# V_3.net
KiCad netlist of a schematic drawn in Altium Designer
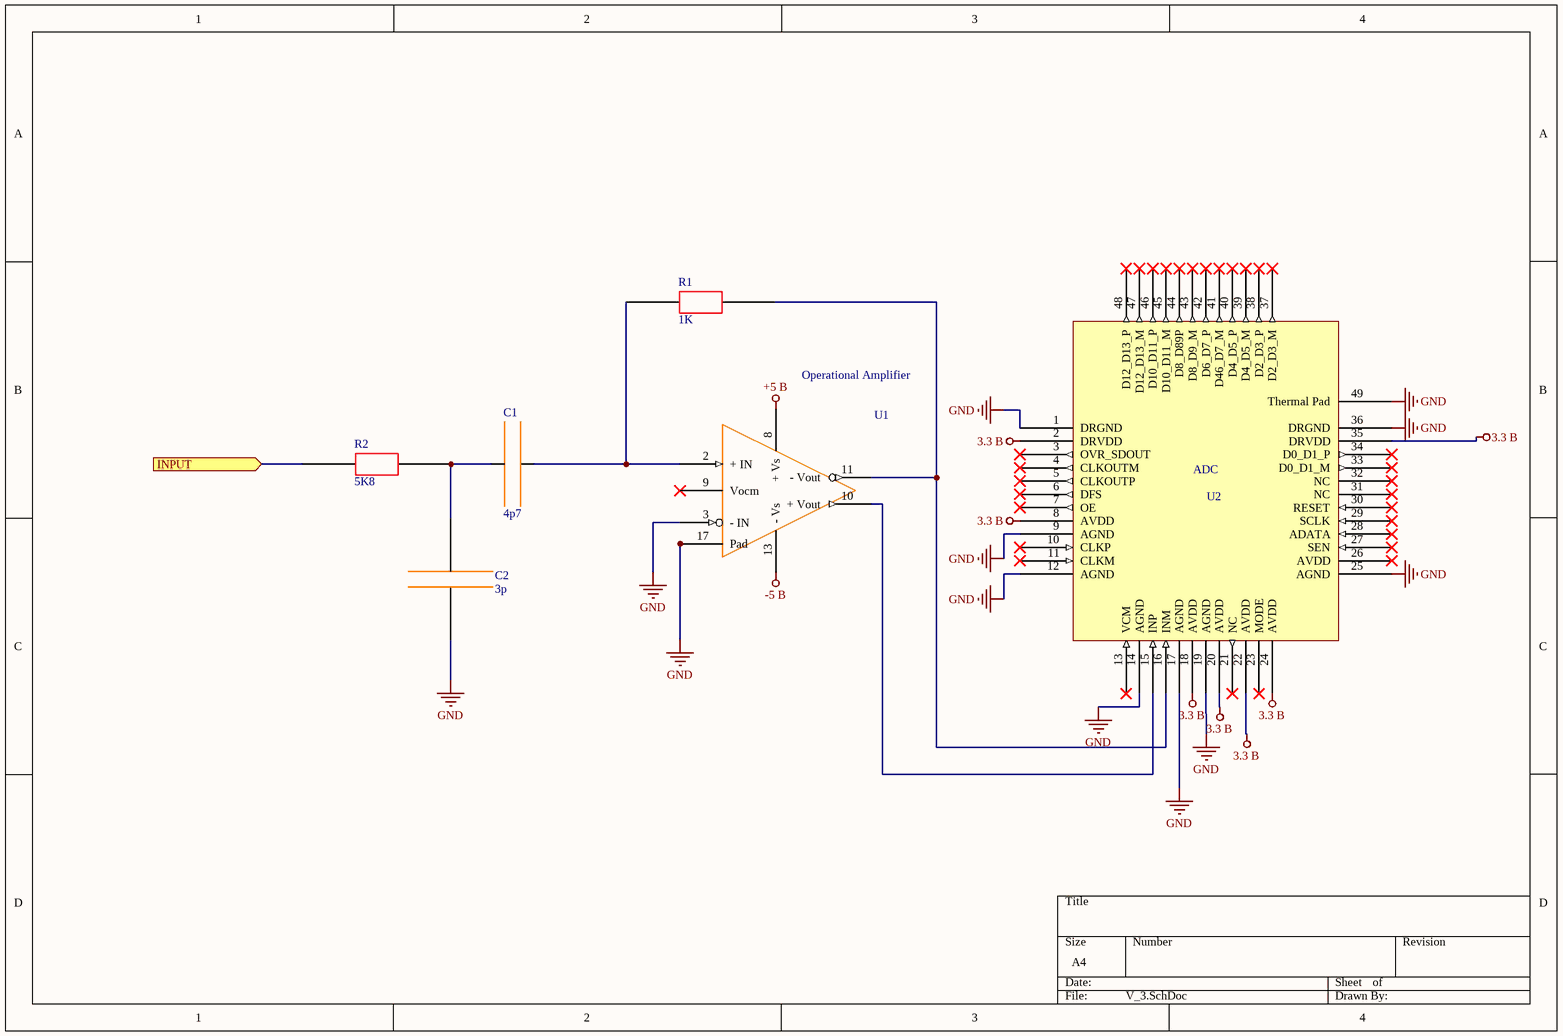
[diagram p0: V_3.SchDoc]

(export (version "E")
  (design (tool "Eeschema 10.0.6"))
  (components
    (comp (ref "C1") (value "4p7") (footprint "V_3:C_0805") (libsource (lib "") (part "Condenser_1")))
    (comp (ref "C2") (value "3p") (footprint "V_3:C_0805") (libsource (lib "V_3") (part "Condenser")))
    (comp (ref "R1") (value "1K") (footprint "V_3:R_0805") (libsource (lib "V_3") (part "Resistor")))
    (comp (ref "R2") (value "5K8") (footprint "V_3:R_0805") (libsource (lib "V_3") (part "Resistor")))
    (comp (ref "U1")
      (value "Operational Amplifier")
      (footprint "V_3:ADA4932-1")
      (libsource (lib "V_3") (part "Operational Amplifier"))
    )
    (comp (ref "U2") (value "ADC") (footprint "V_3:ADS61B49") (libsource (lib "V_3") (part "ADC")))
  )
  (nets
    (net (code "1") (name "+5 B") (class "Default")
      (node (ref "U1") (pin "8") (pinfunction "+_Vs_8") (pintype "passive"))
    )
    (net (code "2") (name "-5 B") (class "Default")
      (node (ref "U1") (pin "13") (pinfunction "-_Vs_13") (pintype "passive"))
    )
    (net (code "3") (name "/INPUT") (class "Default")
      (node (ref "R2") (pin "1") (pinfunction "1_1") (pintype "passive"))
    )
    (net (code "4") (name "3.3 B") (class "Default")
      (node (ref "U2") (pin "18") (pinfunction "AVDD_18") (pintype "power_in"))
      (node (ref "U2") (pin "2") (pinfunction "DRVDD_2") (pintype "power_in"))
      (node (ref "U2") (pin "20") (pinfunction "AVDD_20") (pintype "power_in"))
      (node (ref "U2") (pin "22") (pinfunction "AVDD_22") (pintype "power_in"))
      (node (ref "U2") (pin "24") (pinfunction "AVDD_24") (pintype "power_in"))
      (node (ref "U2") (pin "35") (pinfunction "DRVDD_35") (pintype "power_in"))
      (node (ref "U2") (pin "8") (pinfunction "AVDD_8") (pintype "power_in"))
    )
    (net (code "5") (name "GND") (class "Default")
      (node (ref "C2") (pin "3") (pinfunction "3_3") (pintype "passive"))
      (node (ref "U1") (pin "17") (pinfunction "Pad_17") (pintype "power_in"))
      (node (ref "U1") (pin "3") (pinfunction "-_IN_3") (pintype "input"))
      (node (ref "U2") (pin "1") (pinfunction "DRGND_1") (pintype "power_in"))
      (node (ref "U2") (pin "12") (pinfunction "AGND_12") (pintype "power_in"))
      (node (ref "U2") (pin "14") (pinfunction "AGND_14") (pintype "power_in"))
      (node (ref "U2") (pin "17") (pinfunction "AGND_17") (pintype "power_in"))
      (node (ref "U2") (pin "19") (pinfunction "AGND_19") (pintype "power_in"))
      (node (ref "U2") (pin "25") (pinfunction "AGND_25") (pintype "power_in"))
      (node (ref "U2") (pin "36") (pinfunction "DRGND_36") (pintype "power_in"))
      (node (ref "U2") (pin "49") (pinfunction "Thermal_Pad_49") (pintype "power_in"))
      (node (ref "U2") (pin "9") (pinfunction "AGND_9") (pintype "power_in"))
    )
    (net (code "6") (name "Net-(C1-Pad4)") (class "Default")
      (node (ref "C1") (pin "4") (pinfunction "4_4") (pintype "passive"))
      (node (ref "C2") (pin "4") (pinfunction "4_4") (pintype "passive"))
      (node (ref "R2") (pin "2") (pinfunction "2_2") (pintype "passive"))
    )
    (net (code "7") (name "Net-(U1-+_IN)") (class "Default")
      (node (ref "C1") (pin "3") (pinfunction "3_3") (pintype "passive"))
      (node (ref "R1") (pin "1") (pinfunction "1_1") (pintype "passive"))
      (node (ref "U1") (pin "2") (pinfunction "+_IN_2") (pintype "input"))
    )
    (net (code "8") (name "Net-(U1-+_Vout)") (class "Default")
      (node (ref "U1") (pin "10") (pinfunction "+_Vout_10") (pintype "output"))
      (node (ref "U2") (pin "15") (pinfunction "INP_15") (pintype "input"))
    )
    (net (code "9") (name "Net-(U1--_Vout)") (class "Default")
      (node (ref "R1") (pin "2") (pinfunction "2_2") (pintype "passive"))
      (node (ref "U1") (pin "11") (pinfunction "-_Vout_11") (pintype "output"))
      (node (ref "U2") (pin "16") (pinfunction "INM_16") (pintype "input"))
    )
    (net (code "10") (name "unconnected-(U1-Vocm-Pad9)") (class "Default")
      (node (ref "U1") (pin "9") (pinfunction "Vocm_9") (pintype "passive+no_connect"))
    )
    (net (code "11") (name "unconnected-(U2-ADATA-Pad28)") (class "Default")
      (node (ref "U2") (pin "28") (pinfunction "ADATA_28") (pintype "input+no_connect"))
    )
    (net (code "12") (name "unconnected-(U2-AVDD-Pad26)") (class "Default")
      (node (ref "U2") (pin "26") (pinfunction "AVDD_26") (pintype "power_in+no_connect"))
    )
    (net (code "13") (name "unconnected-(U2-CLKM-Pad11)") (class "Default")
      (node (ref "U2") (pin "11") (pinfunction "CLKM_11") (pintype "input+no_connect"))
    )
    (net (code "14") (name "unconnected-(U2-CLKOUTM-Pad4)") (class "Default")
      (node (ref "U2") (pin "4") (pinfunction "CLKOUTM_4") (pintype "output+no_connect"))
    )
    (net (code "15") (name "unconnected-(U2-CLKOUTP-Pad5)") (class "Default")
      (node (ref "U2") (pin "5") (pinfunction "CLKOUTP_5") (pintype "output+no_connect"))
    )
    (net (code "16") (name "unconnected-(U2-CLKP-Pad10)") (class "Default")
      (node (ref "U2") (pin "10") (pinfunction "CLKP_10") (pintype "input+no_connect"))
    )
    (net (code "17") (name "unconnected-(U2-D0_D1_M-Pad33)") (class "Default")
      (node (ref "U2") (pin "33") (pinfunction "D0_D1_M_33") (pintype "output+no_connect"))
    )
    (net (code "18") (name "unconnected-(U2-D0_D1_P-Pad34)") (class "Default")
      (node (ref "U2") (pin "34") (pinfunction "D0_D1_P_34") (pintype "output+no_connect"))
    )
    (net (code "19") (name "unconnected-(U2-D2_D3_M-Pad37)") (class "Default")
      (node (ref "U2") (pin "37") (pinfunction "D2_D3_M_37") (pintype "output+no_connect"))
    )
    (net (code "20") (name "unconnected-(U2-D2_D3_P-Pad38)") (class "Default")
      (node (ref "U2") (pin "38") (pinfunction "D2_D3_P_38") (pintype "output+no_connect"))
    )
    (net (code "21") (name "unconnected-(U2-D4_D5_M-Pad39)") (class "Default")
      (node (ref "U2") (pin "39") (pinfunction "D4_D5_M_39") (pintype "output+no_connect"))
    )
    (net (code "22") (name "unconnected-(U2-D4_D5_P-Pad40)") (class "Default")
      (node (ref "U2") (pin "40") (pinfunction "D4_D5_P_40") (pintype "output+no_connect"))
    )
    (net (code "23") (name "unconnected-(U2-D6_D7_P-Pad42)") (class "Default")
      (node (ref "U2") (pin "42") (pinfunction "D6_D7_P_42") (pintype "output+no_connect"))
    )
    (net (code "24") (name "unconnected-(U2-D8_D9_M-Pad43)") (class "Default")
      (node (ref "U2") (pin "43") (pinfunction "D8_D9_M_43") (pintype "output+no_connect"))
    )
    (net (code "25") (name "unconnected-(U2-D8_D89P-Pad44)") (class "Default")
      (node (ref "U2") (pin "44") (pinfunction "D8_D89P_44") (pintype "output+no_connect"))
    )
    (net (code "26") (name "unconnected-(U2-D10_D11_M-Pad45)") (class "Default")
      (node (ref "U2") (pin "45") (pinfunction "D10_D11_M_45") (pintype "output+no_connect"))
    )
    (net (code "27") (name "unconnected-(U2-D10_D11_P-Pad46)") (class "Default")
      (node (ref "U2") (pin "46") (pinfunction "D10_D11_P_46") (pintype "output+no_connect"))
    )
    (net (code "28") (name "unconnected-(U2-D12_D13_M-Pad47)") (class "Default")
      (node (ref "U2") (pin "47") (pinfunction "D12_D13_M_47") (pintype "output+no_connect"))
    )
    (net (code "29") (name "unconnected-(U2-D12_D13_P-Pad48)") (class "Default")
      (node (ref "U2") (pin "48") (pinfunction "D12_D13_P_48") (pintype "output+no_connect"))
    )
    (net (code "30") (name "unconnected-(U2-D46_D7_M-Pad41)") (class "Default")
      (node (ref "U2") (pin "41") (pinfunction "D46_D7_M_41") (pintype "output+no_connect"))
    )
    (net (code "31") (name "unconnected-(U2-DFS-Pad6)") (class "Default")
      (node (ref "U2") (pin "6") (pinfunction "DFS_6") (pintype "output+no_connect"))
    )
    (net (code "32") (name "unconnected-(U2-MODE-Pad23)") (class "Default")
      (node (ref "U2") (pin "23") (pinfunction "MODE_23") (pintype "power_in+no_connect"))
    )
    (net (code "33") (name "unconnected-(U2-NC-Pad21)") (class "Default")
      (node (ref "U2") (pin "21") (pinfunction "NC_21") (pintype "output+no_connect"))
    )
    (net (code "34") (name "unconnected-(U2-NC-Pad31)") (class "Default")
      (node (ref "U2") (pin "31") (pinfunction "NC_31") (pintype "power_in+no_connect"))
    )
    (net (code "35") (name "unconnected-(U2-NC-Pad32)") (class "Default")
      (node (ref "U2") (pin "32") (pinfunction "NC_32") (pintype "power_in+no_connect"))
    )
    (net (code "36") (name "unconnected-(U2-OE-Pad7)") (class "Default")
      (node (ref "U2") (pin "7") (pinfunction "OE_7") (pintype "output+no_connect"))
    )
    (net (code "37") (name "unconnected-(U2-OVR_SDOUT-Pad3)") (class "Default")
      (node (ref "U2") (pin "3") (pinfunction "OVR_SDOUT_3") (pintype "output+no_connect"))
    )
    (net (code "38") (name "unconnected-(U2-RESET-Pad30)") (class "Default")
      (node (ref "U2") (pin "30") (pinfunction "RESET_30") (pintype "input+no_connect"))
    )
    (net (code "39") (name "unconnected-(U2-SCLK-Pad29)") (class "Default")
      (node (ref "U2") (pin "29") (pinfunction "SCLK_29") (pintype "input+no_connect"))
    )
    (net (code "40") (name "unconnected-(U2-SEN-Pad27)") (class "Default")
      (node (ref "U2") (pin "27") (pinfunction "SEN_27") (pintype "input+no_connect"))
    )
    (net (code "41") (name "unconnected-(U2-VCM-Pad13)") (class "Default")
      (node (ref "U2") (pin "13") (pinfunction "VCM_13") (pintype "input+no_connect"))
    )
  )
)
